# Harvester.net
KiCad netlist of a schematic drawn in Altium Designer
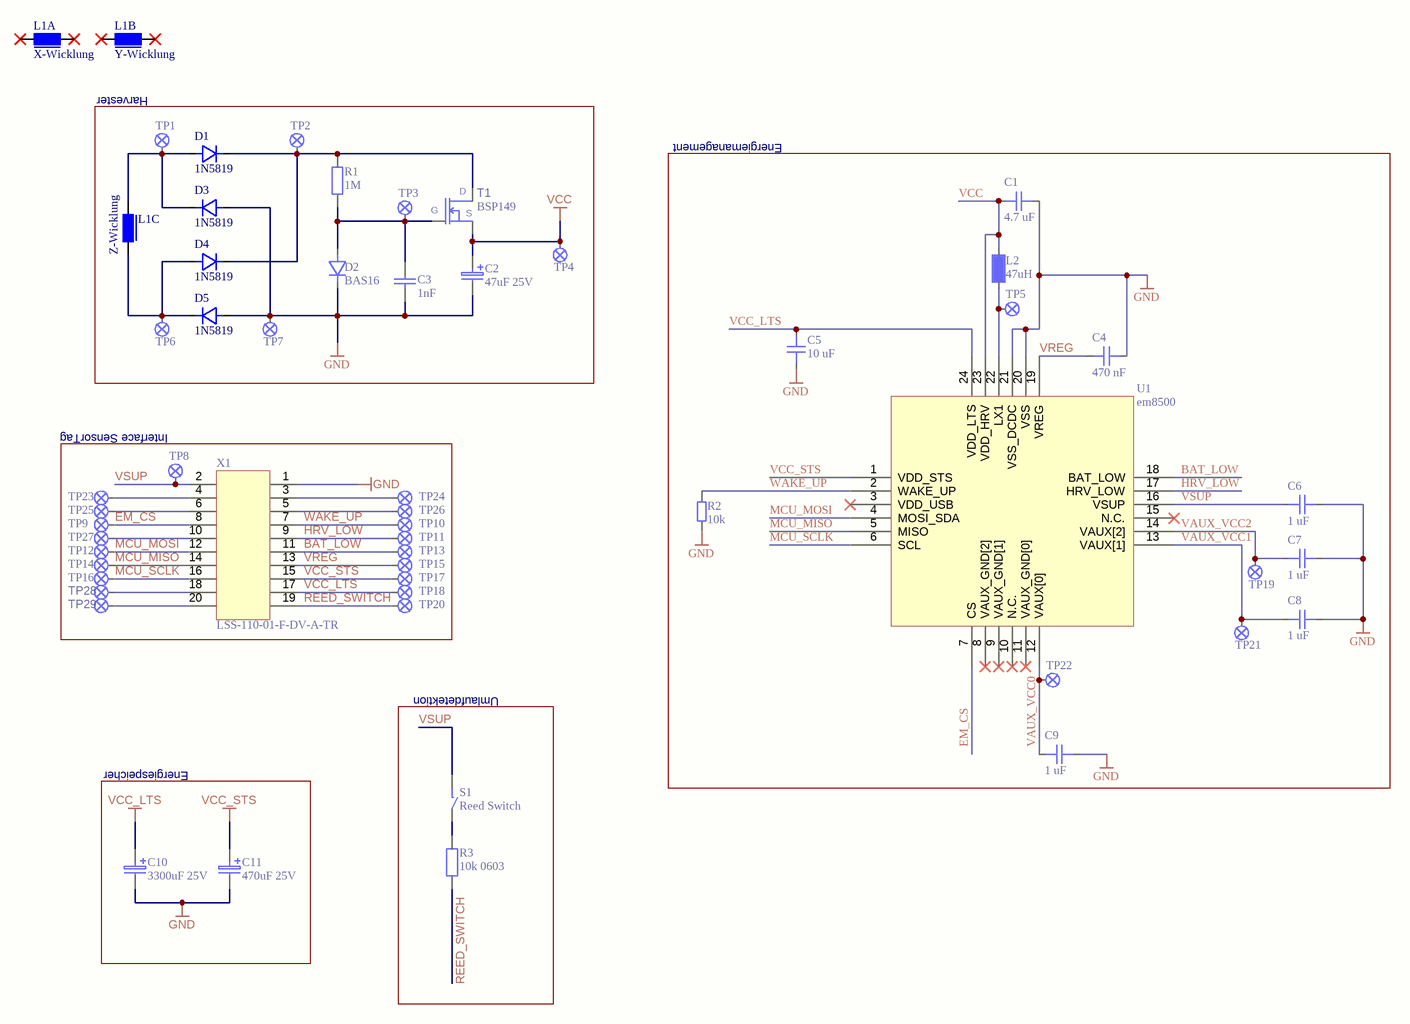
[diagram p0: Harvester.SchDoc]

(export (version "E")
  (design (tool "Eeschema 10.0.6"))
  (components
    (comp (ref "C1")
      (value "4.7 uF")
      (footprint "CHIP 1206")
      (description "Capacitor")
      (fields
        (field (name "MANUFACTURER PART NUMBER") "GRM31CR71E475KA88L")
        (field (name "MANUFACTURER") "Murata")
      )
      (libsource (lib "newlib") (part "C"))
    )
    (comp (ref "C2")
      (value "47uF 25V")
      (footprint "TANT D")
      (description "Capasitor Polarisiert")
      (fields (field (name "MANUFACTURER") "Kemet"))
      (libsource (lib "60 Passiv") (part "C POL"))
    )
    (comp (ref "C3")
      (value "1nF")
      (footprint "CHIP 0603")
      (description "Capacitor 50V")
      (fields (field (name "MANUFACTURER") "AVX"))
      (libsource (lib "60 Passiv") (part "C 50V"))
    )
    (comp (ref "C4")
      (value "470 nF")
      (footprint "CHIP 0603")
      (description "Capacitor")
      (fields
        (field (name "MANUFACTURER PART NUMBER") "CGA3E3X7R1E474K080AB")
        (field (name "MANUFACTURER") "TDK")
      )
      (libsource (lib "newlib") (part "C"))
    )
    (comp (ref "C5")
      (value "10 uF")
      (footprint "CHIP 1206")
      (description "Capacitor")
      (fields
        (field (name "MANUFACTURER PART NUMBER") "CGA5L1X7R1E106K160AC")
        (field (name "MANUFACTURER") "TDK")
      )
      (libsource (lib "newlib") (part "C"))
    )
    (comp (ref "C6")
      (value "1 uF")
      (footprint "CHIP 0603")
      (description "Capacitor")
      (fields
        (field (name "MANUFACTURER PART NUMBER") "CGA3E1X7R1E105K080AC")
        (field (name "MANUFACTURER") "TDK")
      )
      (libsource (lib "newlib") (part "C"))
    )
    (comp (ref "C7")
      (value "1 uF")
      (footprint "CHIP 0603")
      (description "Capacitor")
      (fields
        (field (name "MANUFACTURER PART NUMBER") "CGA3E1X7R1E105K080AC")
        (field (name "MANUFACTURER") "TDK")
      )
      (libsource (lib "newlib") (part "C"))
    )
    (comp (ref "C8")
      (value "1 uF")
      (footprint "CHIP 0603")
      (description "Capacitor")
      (fields
        (field (name "MANUFACTURER PART NUMBER") "CGA3E1X7R1E105K080AC")
        (field (name "MANUFACTURER") "TDK")
      )
      (libsource (lib "newlib") (part "C"))
    )
    (comp (ref "C9")
      (value "1 uF")
      (footprint "CHIP 0603")
      (description "Capacitor")
      (fields
        (field (name "MANUFACTURER PART NUMBER") "CGA3E1X7R1E105K080AC")
        (field (name "MANUFACTURER") "TDK")
      )
      (libsource (lib "newlib") (part "C"))
    )
    (comp (ref "C10")
      (value "3300uF 25V")
      (footprint "JMP 1X2")
      (description "Capasitor Polarisiert")
      (fields (field (name "MANUFACTURER") "Panasonic"))
      (libsource (lib "60 Passiv") (part "C POL"))
    )
    (comp (ref "C11")
      (value "470uF 25V")
      (footprint "JMP 1X2")
      (description "Capasitor Polarisiert")
      (fields (field (name "MANUFACTURER") "Panasonic"))
      (libsource (lib "60 Passiv") (part "C POL"))
    )
    (comp (ref "D1")
      (value "1N5819")
      (footprint "SOD-123")
      (description "Diode")
      (fields (field (name "MANUFACTURER") "Diodes"))
      (libsource (lib "10 Halbleiter Passiv") (part "D"))
    )
    (comp (ref "D2")
      (value "BAS16")
      (footprint "SOT-23")
      (description "Diode")
      (fields (field (name "MANUFACTURER") "ON SEMICONDUCTOR"))
      (libsource (lib "10 Halbleiter Passiv") (part "D"))
    )
    (comp (ref "D3")
      (value "1N5819")
      (footprint "SOD-123")
      (description "Diode")
      (fields (field (name "MANUFACTURER") "Diodes"))
      (libsource (lib "10 Halbleiter Passiv") (part "D"))
    )
    (comp (ref "D4")
      (value "1N5819")
      (footprint "SOD-123")
      (description "Diode")
      (fields (field (name "MANUFACTURER") "Diodes"))
      (libsource (lib "10 Halbleiter Passiv") (part "D"))
    )
    (comp (ref "D5")
      (value "1N5819")
      (footprint "SOD-123")
      (description "Diode")
      (fields (field (name "MANUFACTURER") "Diodes"))
      (libsource (lib "10 Halbleiter Passiv") (part "D"))
    )
    (comp (ref "L1")
      (value "X-Wicklung")
      (footprint "PREMO_3115N_0238J_2")
      (description "Inductor")
      (libsource (lib "60 Passiv") (part "PREMO 3015 0238J 2"))
    )
    (comp (ref "L2")
      (value "47uH")
      (footprint "CHIP 0805")
      (description "Ind")
      (fields
        (field (name "MANUFACTURER PART NUMBER") "0805PS-473KLB")
        (field (name "MANUFACTURER") "Coilcraft")
      )
      (libsource (lib "newlib") (part "L"))
    )
    (comp (ref "R1")
      (value "1M")
      (footprint "CHIP 0603")
      (description "Resistor")
      (fields (field (name "MANUFACTURER") "Vishay"))
      (libsource (lib "60 Passiv") (part "R"))
    )
    (comp (ref "R2")
      (value "10k")
      (footprint "CHIP 0603")
      (description "Resistor")
      (fields
        (field (name "MANUFACTURER PART NUMBER") "CRCW06031K00FKEA")
        (field (name "MANUFACTURER") "Vishay")
      )
      (libsource (lib "newlib") (part "R"))
    )
    (comp (ref "R3")
      (value "10k 0603")
      (footprint "CHIP 0603")
      (description "Resistor")
      (fields (field (name "MANUFACTURER") "Vishay"))
      (libsource (lib "60 Passiv") (part "R"))
    )
    (comp (ref "S1")
      (value "Reed Switch")
      (footprint "MK16-C-2")
      (description "Switch Micro Normal Open")
      (fields (field (name "MANUFACTURER") "STANDEXMEDER"))
      (libsource (lib "80 Stecker & Mech") (part "SWITCH MICRO NO"))
    )
    (comp (ref "T1")
      (value "BSP149")
      (footprint "SOT-223")
      (description "MOSFET N-Kanal")
      (fields (field (name "MANUFACTURER") "Infineon"))
      (libsource (lib "20 Halbleiter Analog") (part "BSP149"))
    )
    (comp (ref "TP1")
      (value "TP")
      (footprint "TP")
      (description "Testpoint SMD")
      (libsource (lib "80 Stecker & Mech") (part "TP_SMD"))
    )
    (comp (ref "TP2")
      (value "TP")
      (footprint "TP")
      (description "Testpoint SMD")
      (libsource (lib "80 Stecker & Mech") (part "TP_SMD"))
    )
    (comp (ref "TP3")
      (value "TP")
      (footprint "TP")
      (description "Testpoint SMD")
      (libsource (lib "80 Stecker & Mech") (part "TP_SMD"))
    )
    (comp (ref "TP4")
      (value "TP")
      (footprint "TP")
      (description "Testpoint SMD")
      (libsource (lib "80 Stecker & Mech") (part "TP_SMD"))
    )
    (comp (ref "TP5")
      (value "TP")
      (footprint "TP")
      (description "Testpoint SMD")
      (libsource (lib "80 Stecker & Mech") (part "TP_SMD"))
    )
    (comp (ref "TP6")
      (value "TP")
      (footprint "TP")
      (description "Testpoint SMD")
      (libsource (lib "80 Stecker & Mech") (part "TP_SMD"))
    )
    (comp (ref "TP7")
      (value "TP")
      (footprint "TP")
      (description "Testpoint SMD")
      (libsource (lib "80 Stecker & Mech") (part "TP_SMD"))
    )
    (comp (ref "TP8")
      (value "TP")
      (footprint "TP")
      (description "Testpoint SMD")
      (libsource (lib "80 Stecker & Mech") (part "TP_SMD"))
    )
    (comp (ref "TP9")
      (value "TP")
      (footprint "TP")
      (description "Testpoint SMD")
      (libsource (lib "80 Stecker & Mech") (part "TP_SMD"))
    )
    (comp (ref "TP10")
      (value "TP")
      (footprint "TP")
      (description "Testpoint SMD")
      (libsource (lib "80 Stecker & Mech") (part "TP_SMD"))
    )
    (comp (ref "TP11")
      (value "TP")
      (footprint "TP")
      (description "Testpoint SMD")
      (libsource (lib "80 Stecker & Mech") (part "TP_SMD"))
    )
    (comp (ref "TP12")
      (value "TP")
      (footprint "TP")
      (description "Testpoint SMD")
      (libsource (lib "80 Stecker & Mech") (part "TP_SMD"))
    )
    (comp (ref "TP13")
      (value "TP")
      (footprint "TP")
      (description "Testpoint SMD")
      (libsource (lib "80 Stecker & Mech") (part "TP_SMD"))
    )
    (comp (ref "TP14")
      (value "TP")
      (footprint "TP")
      (description "Testpoint SMD")
      (libsource (lib "80 Stecker & Mech") (part "TP_SMD"))
    )
    (comp (ref "TP15")
      (value "TP")
      (footprint "TP")
      (description "Testpoint SMD")
      (libsource (lib "80 Stecker & Mech") (part "TP_SMD"))
    )
    (comp (ref "TP16")
      (value "TP")
      (footprint "TP")
      (description "Testpoint SMD")
      (libsource (lib "80 Stecker & Mech") (part "TP_SMD"))
    )
    (comp (ref "TP17")
      (value "TP")
      (footprint "TP")
      (description "Testpoint SMD")
      (libsource (lib "80 Stecker & Mech") (part "TP_SMD"))
    )
    (comp (ref "TP18")
      (value "TP")
      (footprint "TP")
      (description "Testpoint SMD")
      (libsource (lib "80 Stecker & Mech") (part "TP_SMD"))
    )
    (comp (ref "TP19")
      (value "TP")
      (footprint "TP")
      (description "Testpoint SMD")
      (libsource (lib "80 Stecker & Mech") (part "TP_SMD"))
    )
    (comp (ref "TP20")
      (value "TP")
      (footprint "TP")
      (description "Testpoint SMD")
      (libsource (lib "80 Stecker & Mech") (part "TP_SMD"))
    )
    (comp (ref "TP21")
      (value "TP")
      (footprint "TP")
      (description "Testpoint SMD")
      (libsource (lib "80 Stecker & Mech") (part "TP_SMD"))
    )
    (comp (ref "TP22")
      (value "TP")
      (footprint "TP")
      (description "Testpoint SMD")
      (libsource (lib "80 Stecker & Mech") (part "TP_SMD"))
    )
    (comp (ref "TP23")
      (value "TP")
      (footprint "TP")
      (description "Testpoint SMD")
      (libsource (lib "80 Stecker & Mech") (part "TP_SMD"))
    )
    (comp (ref "TP24")
      (value "TP")
      (footprint "TP")
      (description "Testpoint SMD")
      (libsource (lib "80 Stecker & Mech") (part "TP_SMD"))
    )
    (comp (ref "TP25")
      (value "TP")
      (footprint "TP")
      (description "Testpoint SMD")
      (libsource (lib "80 Stecker & Mech") (part "TP_SMD"))
    )
    (comp (ref "TP26")
      (value "TP")
      (footprint "TP")
      (description "Testpoint SMD")
      (libsource (lib "80 Stecker & Mech") (part "TP_SMD"))
    )
    (comp (ref "TP27")
      (value "TP")
      (footprint "TP")
      (description "Testpoint SMD")
      (libsource (lib "80 Stecker & Mech") (part "TP_SMD"))
    )
    (comp (ref "TP28")
      (value "TP")
      (footprint "TP")
      (description "Testpoint SMD")
      (libsource (lib "80 Stecker & Mech") (part "TP_SMD"))
    )
    (comp (ref "TP29")
      (value "TP")
      (footprint "TP")
      (description "Testpoint SMD")
      (libsource (lib "80 Stecker & Mech") (part "TP_SMD"))
    )
    (comp (ref "U1")
      (value "em8500")
      (footprint "QFN-24")
      (fields
        (field (name "MANUFACTURER") "EM Microelectronic")
        (field (name "MANUFACTURER PART NUMBER") "EM8500")
      )
      (libsource (lib "Schlib1") (part "em8500"))
    )
    (comp (ref "X1")
      (value "LSS-110-01-F-DV-A-TR")
      (footprint "HEADER SMD 2x10 0.635mm")
      (description "Header 100 mil 20 Pol")
      (fields (field (name "MANUFACTURER") "Samtech"))
      (libsource (lib "80 Stecker & Mech") (part "HDR 20 POL ABW"))
    )
  )
  (nets
    (net (code "1") (name "/BAT_LOW") (class "Default")
      (node (ref "TP13") (pin "1") (pinfunction "1_1") (pintype "passive"))
      (node (ref "U1") (pin "18") (pinfunction "BAT_LOW_18") (pintype "passive"))
      (node (ref "X1") (pin "11") (pinfunction "11_11") (pintype "passive"))
    )
    (net (code "2") (name "/EM_CS") (class "Default")
      (node (ref "TP9") (pin "1") (pinfunction "1_1") (pintype "passive"))
      (node (ref "U1") (pin "7") (pinfunction "CS_7") (pintype "passive"))
      (node (ref "X1") (pin "8") (pinfunction "8_8") (pintype "passive"))
    )
    (net (code "3") (name "/HRV_LOW") (class "Default")
      (node (ref "TP11") (pin "1") (pinfunction "1_1") (pintype "passive"))
      (node (ref "U1") (pin "17") (pinfunction "HRV_LOW_17") (pintype "passive"))
      (node (ref "X1") (pin "9") (pinfunction "9_9") (pintype "passive"))
    )
    (net (code "4") (name "/MCU_MISO") (class "Default")
      (node (ref "TP14") (pin "1") (pinfunction "1_1") (pintype "passive"))
      (node (ref "U1") (pin "5") (pinfunction "MISO_5") (pintype "passive"))
      (node (ref "X1") (pin "14") (pinfunction "14_14") (pintype "passive"))
    )
    (net (code "5") (name "/MCU_MOSI") (class "Default")
      (node (ref "TP12") (pin "1") (pinfunction "1_1") (pintype "passive"))
      (node (ref "U1") (pin "4") (pinfunction "MOSI_SDA_4") (pintype "passive"))
      (node (ref "X1") (pin "12") (pinfunction "12_12") (pintype "passive"))
    )
    (net (code "6") (name "/MCU_SCLK") (class "Default")
      (node (ref "TP16") (pin "1") (pinfunction "1_1") (pintype "passive"))
      (node (ref "U1") (pin "6") (pinfunction "SCL_6") (pintype "passive"))
      (node (ref "X1") (pin "16") (pinfunction "16_16") (pintype "passive"))
    )
    (net (code "7") (name "/REED_SWITCH") (class "Default")
      (node (ref "R3") (pin "1") (pinfunction "1_1") (pintype "passive"))
      (node (ref "TP20") (pin "1") (pinfunction "1_1") (pintype "passive"))
      (node (ref "X1") (pin "19") (pinfunction "19_19") (pintype "passive"))
    )
    (net (code "8") (name "/VAUX_VCC0") (class "Default")
      (node (ref "C9") (pin "1") (pinfunction "1_1") (pintype "passive"))
      (node (ref "TP22") (pin "1") (pinfunction "1_1") (pintype "passive"))
      (node (ref "U1") (pin "12") (pinfunction "VAUX[0]_12") (pintype "passive"))
    )
    (net (code "9") (name "/VAUX_VCC1") (class "Default")
      (node (ref "C8") (pin "1") (pinfunction "1_1") (pintype "passive"))
      (node (ref "TP21") (pin "1") (pinfunction "1_1") (pintype "passive"))
      (node (ref "U1") (pin "13") (pinfunction "VAUX[1]_13") (pintype "passive"))
    )
    (net (code "10") (name "/VAUX_VCC2") (class "Default")
      (node (ref "C7") (pin "1") (pinfunction "1_1") (pintype "passive"))
      (node (ref "TP19") (pin "1") (pinfunction "1_1") (pintype "passive"))
      (node (ref "U1") (pin "14") (pinfunction "VAUX[2]_14") (pintype "passive"))
    )
    (net (code "11") (name "/VREG") (class "Default")
      (node (ref "C4") (pin "1") (pinfunction "1_1") (pintype "passive"))
      (node (ref "TP15") (pin "1") (pinfunction "1_1") (pintype "passive"))
      (node (ref "U1") (pin "19") (pinfunction "VREG_19") (pintype "passive"))
      (node (ref "X1") (pin "13") (pinfunction "13_13") (pintype "passive"))
    )
    (net (code "12") (name "/VSUP") (class "Default")
      (node (ref "C6") (pin "1") (pinfunction "1_1") (pintype "passive"))
      (node (ref "S1") (pin "2") (pinfunction "2_2") (pintype "passive"))
      (node (ref "TP8") (pin "1") (pinfunction "1_1") (pintype "passive"))
      (node (ref "U1") (pin "16") (pinfunction "VSUP_16") (pintype "passive"))
      (node (ref "X1") (pin "2") (pinfunction "2_2") (pintype "passive"))
    )
    (net (code "13") (name "/WAKE_UP") (class "Default")
      (node (ref "R2") (pin "1") (pinfunction "1_1") (pintype "passive"))
      (node (ref "TP10") (pin "1") (pinfunction "1_1") (pintype "passive"))
      (node (ref "U1") (pin "2") (pinfunction "WAKE_UP_2") (pintype "passive"))
      (node (ref "X1") (pin "7") (pinfunction "7_7") (pintype "passive"))
    )
    (net (code "14") (name "GND") (class "Default")
      (node (ref "C1") (pin "2") (pinfunction "2_2") (pintype "passive"))
      (node (ref "C10") (pin "2") (pinfunction "NEG_2") (pintype "passive"))
      (node (ref "C11") (pin "2") (pinfunction "NEG_2") (pintype "passive"))
      (node (ref "C2") (pin "2") (pinfunction "NEG_2") (pintype "passive"))
      (node (ref "C3") (pin "1") (pinfunction "1_1") (pintype "passive"))
      (node (ref "C4") (pin "2") (pinfunction "2_2") (pintype "passive"))
      (node (ref "C5") (pin "2") (pinfunction "2_2") (pintype "passive"))
      (node (ref "C6") (pin "2") (pinfunction "2_2") (pintype "passive"))
      (node (ref "C7") (pin "2") (pinfunction "2_2") (pintype "passive"))
      (node (ref "C8") (pin "2") (pinfunction "2_2") (pintype "passive"))
      (node (ref "C9") (pin "2") (pinfunction "2_2") (pintype "passive"))
      (node (ref "D2") (pin "2") (pinfunction "K_2") (pintype "passive"))
      (node (ref "D3") (pin "1") (pinfunction "A_1") (pintype "passive"))
      (node (ref "D5") (pin "1") (pinfunction "A_1") (pintype "passive"))
      (node (ref "R2") (pin "2") (pinfunction "2_2") (pintype "passive"))
      (node (ref "TP7") (pin "1") (pinfunction "1_1") (pintype "passive"))
      (node (ref "U1") (pin "20") (pinfunction "VSS_20") (pintype "passive"))
      (node (ref "U1") (pin "21") (pinfunction "VSS_DCDC_21") (pintype "passive"))
      (node (ref "X1") (pin "1") (pinfunction "1_1") (pintype "passive"))
    )
    (net (code "15") (name "Net-(D1-A)") (class "Default")
      (node (ref "D1") (pin "1") (pinfunction "A_1") (pintype "passive"))
      (node (ref "D3") (pin "2") (pinfunction "K_2") (pintype "passive"))
      (node (ref "L1") (pin "8") (pinfunction "8_8") (pintype "passive"))
      (node (ref "TP1") (pin "1") (pinfunction "1_1") (pintype "passive"))
    )
    (net (code "16") (name "Net-(D1-K)") (class "Default")
      (node (ref "D1") (pin "2") (pinfunction "K_2") (pintype "passive"))
      (node (ref "D4") (pin "2") (pinfunction "K_2") (pintype "passive"))
      (node (ref "R1") (pin "2") (pinfunction "2_2") (pintype "passive"))
      (node (ref "T1") (pin "3") (pinfunction "S_3") (pintype "passive"))
      (node (ref "TP2") (pin "1") (pinfunction "1_1") (pintype "passive"))
    )
    (net (code "17") (name "Net-(D2-A)") (class "Default")
      (node (ref "C3") (pin "2") (pinfunction "2_2") (pintype "passive"))
      (node (ref "D2") (pin "1") (pinfunction "A_1") (pintype "passive"))
      (node (ref "R1") (pin "1") (pinfunction "1_1") (pintype "passive"))
      (node (ref "T1") (pin "1") (pinfunction "G_1") (pintype "passive"))
      (node (ref "TP3") (pin "1") (pinfunction "1_1") (pintype "passive"))
    )
    (net (code "18") (name "Net-(D4-A)") (class "Default")
      (node (ref "D4") (pin "1") (pinfunction "A_1") (pintype "passive"))
      (node (ref "D5") (pin "2") (pinfunction "K_2") (pintype "passive"))
      (node (ref "L1") (pin "4") (pinfunction "4_4") (pintype "passive"))
      (node (ref "TP6") (pin "1") (pinfunction "1_1") (pintype "passive"))
    )
    (net (code "19") (name "Net-(R3-Pad2)") (class "Default")
      (node (ref "R3") (pin "2") (pinfunction "2_2") (pintype "passive"))
      (node (ref "S1") (pin "1") (pinfunction "1_1") (pintype "passive"))
    )
    (net (code "20") (name "Net-(TP23-Pad1)") (class "Default")
      (node (ref "TP23") (pin "1") (pinfunction "1_1") (pintype "passive"))
      (node (ref "X1") (pin "4") (pinfunction "4_4") (pintype "passive"))
    )
    (net (code "21") (name "Net-(TP24-Pad1)") (class "Default")
      (node (ref "TP24") (pin "1") (pinfunction "1_1") (pintype "passive"))
      (node (ref "X1") (pin "3") (pinfunction "3_3") (pintype "passive"))
    )
    (net (code "22") (name "Net-(TP25-Pad1)") (class "Default")
      (node (ref "TP25") (pin "1") (pinfunction "1_1") (pintype "passive"))
      (node (ref "X1") (pin "6") (pinfunction "6_6") (pintype "passive"))
    )
    (net (code "23") (name "Net-(TP26-Pad1)") (class "Default")
      (node (ref "TP26") (pin "1") (pinfunction "1_1") (pintype "passive"))
      (node (ref "X1") (pin "5") (pinfunction "5_5") (pintype "passive"))
    )
    (net (code "24") (name "Net-(TP27-Pad1)") (class "Default")
      (node (ref "TP27") (pin "1") (pinfunction "1_1") (pintype "passive"))
      (node (ref "X1") (pin "10") (pinfunction "10_10") (pintype "passive"))
    )
    (net (code "25") (name "Net-(TP28-Pad1)") (class "Default")
      (node (ref "TP28") (pin "1") (pinfunction "1_1") (pintype "passive"))
      (node (ref "X1") (pin "18") (pinfunction "18_18") (pintype "passive"))
    )
    (net (code "26") (name "Net-(TP29-Pad1)") (class "Default")
      (node (ref "TP29") (pin "1") (pinfunction "1_1") (pintype "passive"))
      (node (ref "X1") (pin "20") (pinfunction "20_20") (pintype "passive"))
    )
    (net (code "27") (name "Net-(U1-LX1)") (class "Default")
      (node (ref "L2") (pin "1") (pinfunction "1_1") (pintype "passive"))
      (node (ref "TP5") (pin "1") (pinfunction "1_1") (pintype "passive"))
      (node (ref "U1") (pin "22") (pinfunction "LX1_22") (pintype "passive"))
    )
    (net (code "28") (name "VCC") (class "Default")
      (node (ref "C1") (pin "1") (pinfunction "1_1") (pintype "passive"))
      (node (ref "C2") (pin "1") (pinfunction "POS_1") (pintype "passive"))
      (node (ref "L2") (pin "2") (pinfunction "2_2") (pintype "passive"))
      (node (ref "T1") (pin "2") (pinfunction "D_2") (pintype "passive"))
      (node (ref "TP4") (pin "1") (pinfunction "1_1") (pintype "passive"))
      (node (ref "U1") (pin "23") (pinfunction "VDD_HRV_23") (pintype "passive"))
    )
    (net (code "29") (name "VCC_LTS") (class "Default")
      (node (ref "C10") (pin "1") (pinfunction "POS_1") (pintype "passive"))
      (node (ref "C5") (pin "1") (pinfunction "1_1") (pintype "passive"))
      (node (ref "TP18") (pin "1") (pinfunction "1_1") (pintype "passive"))
      (node (ref "U1") (pin "24") (pinfunction "VDD_LTS_24") (pintype "passive"))
      (node (ref "X1") (pin "17") (pinfunction "17_17") (pintype "passive"))
    )
    (net (code "30") (name "VCC_STS") (class "Default")
      (node (ref "C11") (pin "1") (pinfunction "POS_1") (pintype "passive"))
      (node (ref "TP17") (pin "1") (pinfunction "1_1") (pintype "passive"))
      (node (ref "U1") (pin "1") (pinfunction "VDD_STS_1") (pintype "passive"))
      (node (ref "X1") (pin "15") (pinfunction "15_15") (pintype "passive"))
    )
    (net (code "31") (name "unconnected-(L1-Pad2)") (class "Default")
      (node (ref "L1") (pin "2") (pinfunction "2_2") (pintype "passive+no_connect"))
    )
    (net (code "32") (name "unconnected-(L1-Pad3)") (class "Default")
      (node (ref "L1") (pin "3") (pinfunction "3_3") (pintype "passive+no_connect"))
    )
    (net (code "33") (name "unconnected-(L1-Pad6)") (class "Default")
      (node (ref "L1") (pin "6") (pinfunction "6_6") (pintype "passive+no_connect"))
    )
    (net (code "34") (name "unconnected-(L1-Pad7)") (class "Default")
      (node (ref "L1") (pin "7") (pinfunction "7_7") (pintype "passive+no_connect"))
    )
    (net (code "35") (name "unconnected-(T1-D-Pad4)") (class "Default")
      (node (ref "T1") (pin "4") (pinfunction "D_4") (pintype "passive"))
    )
    (net (code "36") (name "unconnected-(U1-N.C.-Pad10)") (class "Default")
      (node (ref "U1") (pin "10") (pinfunction "N.C._10") (pintype "passive+no_connect"))
    )
    (net (code "37") (name "unconnected-(U1-N.C.-Pad15)") (class "Default")
      (node (ref "U1") (pin "15") (pinfunction "N.C._15") (pintype "passive+no_connect"))
    )
    (net (code "38") (name "unconnected-(U1-VAUX_GND[0]-Pad11)") (class "Default")
      (node (ref "U1") (pin "11") (pinfunction "VAUX_GND[0]_11") (pintype "passive+no_connect"))
    )
    (net (code "39") (name "unconnected-(U1-VAUX_GND[1]-Pad9)") (class "Default")
      (node (ref "U1") (pin "9") (pinfunction "VAUX_GND[1]_9") (pintype "passive+no_connect"))
    )
    (net (code "40") (name "unconnected-(U1-VAUX_GND[2]-Pad8)") (class "Default")
      (node (ref "U1") (pin "8") (pinfunction "VAUX_GND[2]_8") (pintype "passive+no_connect"))
    )
    (net (code "41") (name "unconnected-(U1-VDD_USB-Pad3)") (class "Default")
      (node (ref "U1") (pin "3") (pinfunction "VDD_USB_3") (pintype "passive+no_connect"))
    )
  )
)
